# PWA_1_0.net
KiCad netlist of a schematic drawn in EAGLE
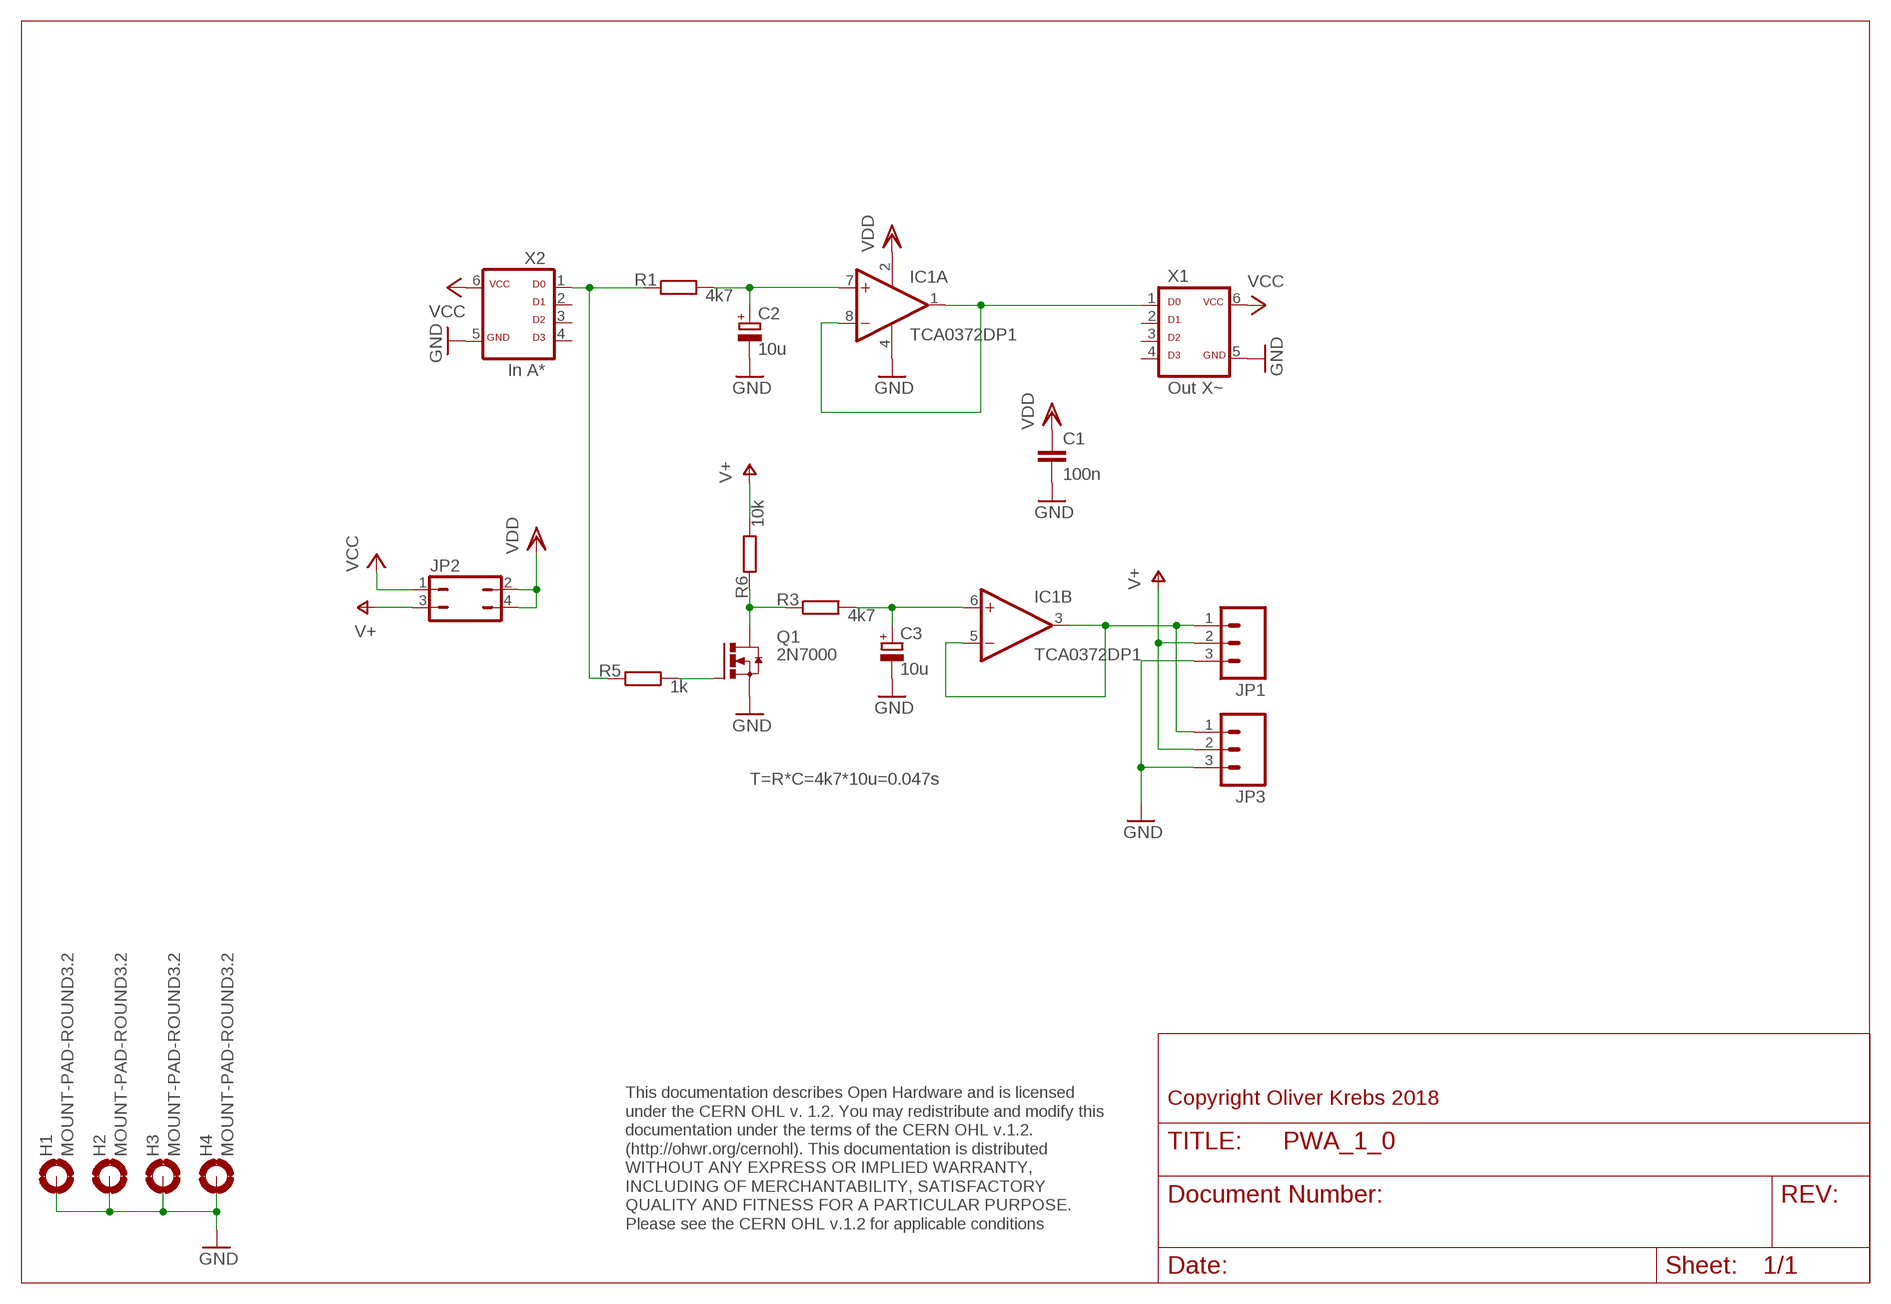
[diagram p0: schematic, sheet 1]

(export (version "E")
  (design (tool "Eeschema 10.0.6"))
  (components
    (comp (ref "C1")
      (value "100n")
      (footprint "eagle-import:C050-025X075")
      (libsource (lib "eagle-import") (part "C-EU050-025X075"))
    )
    (comp (ref "C2")
      (value "10u")
      (footprint "eagle-import:E2-4")
      (libsource (lib "eagle-import") (part "CPOL-EUE2-4"))
    )
    (comp (ref "C3")
      (value "10u")
      (footprint "eagle-import:E2-4")
      (libsource (lib "eagle-import") (part "CPOL-EUE2-4"))
    )
    (comp (ref "H1")
      (value "MOUNT-PAD-ROUND3.2")
      (footprint "eagle-import:3,2-PAD")
      (libsource (lib "eagle-import") (part "MOUNT-PAD-ROUND3.2"))
    )
    (comp (ref "H2")
      (value "MOUNT-PAD-ROUND3.2")
      (footprint "eagle-import:3,2-PAD")
      (libsource (lib "eagle-import") (part "MOUNT-PAD-ROUND3.2"))
    )
    (comp (ref "H3")
      (value "MOUNT-PAD-ROUND3.2")
      (footprint "eagle-import:3,2-PAD")
      (libsource (lib "eagle-import") (part "MOUNT-PAD-ROUND3.2"))
    )
    (comp (ref "H4")
      (value "MOUNT-PAD-ROUND3.2")
      (footprint "eagle-import:3,2-PAD")
      (libsource (lib "eagle-import") (part "MOUNT-PAD-ROUND3.2"))
    )
    (comp (ref "IC1")
      (value "TCA0372DP1")
      (footprint "eagle-import:DIL08")
      (libsource (lib "eagle-import") (part "TCA0372DP1"))
    )
    (comp (ref "JP1")
      (value "M03PTH")
      (footprint "eagle-import:1X03")
      (libsource (lib "eagle-import") (part "M03PTH"))
    )
    (comp (ref "JP2")
      (value "JP2Q")
      (footprint "eagle-import:JP2Q")
      (libsource (lib "eagle-import") (part "JP2Q"))
    )
    (comp (ref "JP3")
      (value "M03BIG_5.08")
      (footprint "eagle-import:1X03_BIG_5.08")
      (libsource (lib "eagle-import") (part "M03BIG_5.08"))
    )
    (comp (ref "Q1")
      (value "2N7000")
      (footprint "eagle-import:TO92-LINE")
      (libsource (lib "eagle-import") (part "2N7000"))
    )
    (comp (ref "R1")
      (value "4k7")
      (footprint "eagle-import:0207_10")
      (libsource (lib "eagle-import") (part "R-EU_0207/10"))
    )
    (comp (ref "R3")
      (value "4k7")
      (footprint "eagle-import:0207_10")
      (libsource (lib "eagle-import") (part "R-EU_0207/10"))
    )
    (comp (ref "R5")
      (value "1k")
      (footprint "eagle-import:0207_10")
      (libsource (lib "eagle-import") (part "R-EU_0207/10"))
    )
    (comp (ref "R6")
      (value "10k")
      (footprint "eagle-import:0207_10")
      (libsource (lib "eagle-import") (part "R-EU_0207/10"))
    )
    (comp (ref "X1")
      (value "Out X~")
      (footprint "eagle-import:ML-6")
      (libsource (lib "eagle-import") (part "ML6D"))
    )
    (comp (ref "X2")
      (value "In A*")
      (footprint "eagle-import:ML-6")
      (libsource (lib "eagle-import") (part "ML6D"))
    )
  )
  (nets
    (net (code "1") (name "GND") (class "Default")
      (node (ref "C1") (pin "2") (pinfunction "2_2") (pintype "passive"))
      (node (ref "C2") (pin "-") (pinfunction "-_-") (pintype "passive"))
      (node (ref "C3") (pin "-") (pinfunction "-_-") (pintype "passive"))
      (node (ref "H1") (pin "B3,2") (pinfunction "MOUNT_B3,2") (pintype "passive"))
      (node (ref "H2") (pin "B3,2") (pinfunction "MOUNT_B3,2") (pintype "passive"))
      (node (ref "H3") (pin "B3,2") (pinfunction "MOUNT_B3,2") (pintype "passive"))
      (node (ref "H4") (pin "B3,2") (pinfunction "MOUNT_B3,2") (pintype "passive"))
      (node (ref "IC1") (pin "4") (pinfunction "GND_4") (pintype "power_in"))
      (node (ref "JP1") (pin "3") (pinfunction "3_3") (pintype "passive"))
      (node (ref "JP3") (pin "3") (pinfunction "3_3") (pintype "passive"))
      (node (ref "Q1") (pin "3") (pinfunction "S_3") (pintype "passive"))
      (node (ref "X1") (pin "5") (pinfunction "5_5") (pintype "passive"))
      (node (ref "X2") (pin "5") (pinfunction "5_5") (pintype "passive"))
    )
    (net (code "2") (name "Net-(IC1A-+IN)") (class "Default")
      (node (ref "C2") (pin "+") (pinfunction "+_+") (pintype "passive"))
      (node (ref "IC1") (pin "7") (pinfunction "+IN_7") (pintype "input"))
      (node (ref "R1") (pin "2") (pinfunction "2_2") (pintype "passive"))
    )
    (net (code "3") (name "Net-(IC1A--IN)") (class "Default")
      (node (ref "IC1") (pin "1") (pinfunction "OUT_1") (pintype "output"))
      (node (ref "IC1") (pin "8") (pinfunction "-IN_8") (pintype "input"))
      (node (ref "X1") (pin "1") (pinfunction "1_1") (pintype "passive"))
    )
    (net (code "4") (name "Net-(IC1B-+IN)") (class "Default")
      (node (ref "C3") (pin "+") (pinfunction "+_+") (pintype "passive"))
      (node (ref "IC1") (pin "6") (pinfunction "+IN_6") (pintype "input"))
      (node (ref "R3") (pin "2") (pinfunction "2_2") (pintype "passive"))
    )
    (net (code "5") (name "Net-(IC1B--IN)") (class "Default")
      (node (ref "IC1") (pin "3") (pinfunction "OUT_3") (pintype "output"))
      (node (ref "IC1") (pin "5") (pinfunction "-IN_5") (pintype "input"))
      (node (ref "JP1") (pin "1") (pinfunction "1_1") (pintype "passive"))
      (node (ref "JP3") (pin "1") (pinfunction "1_1") (pintype "passive"))
    )
    (net (code "6") (name "Net-(Q1-D)") (class "Default")
      (node (ref "Q1") (pin "1") (pinfunction "D_1") (pintype "passive"))
      (node (ref "R3") (pin "1") (pinfunction "1_1") (pintype "passive"))
      (node (ref "R6") (pin "1") (pinfunction "1_1") (pintype "passive"))
    )
    (net (code "7") (name "Net-(Q1-G)") (class "Default")
      (node (ref "Q1") (pin "2") (pinfunction "G_2") (pintype "passive"))
      (node (ref "R5") (pin "2") (pinfunction "2_2") (pintype "passive"))
    )
    (net (code "8") (name "Net-(R1-Pad1)") (class "Default")
      (node (ref "R1") (pin "1") (pinfunction "1_1") (pintype "passive"))
      (node (ref "R5") (pin "1") (pinfunction "1_1") (pintype "passive"))
      (node (ref "X2") (pin "1") (pinfunction "1_1") (pintype "passive"))
    )
    (net (code "9") (name "V+") (class "Default")
      (node (ref "JP1") (pin "2") (pinfunction "2_2") (pintype "passive"))
      (node (ref "JP2") (pin "3") (pinfunction "3_3") (pintype "passive"))
      (node (ref "JP3") (pin "2") (pinfunction "2_2") (pintype "passive"))
      (node (ref "R6") (pin "2") (pinfunction "2_2") (pintype "passive"))
    )
    (net (code "10") (name "VCC") (class "Default")
      (node (ref "JP2") (pin "1") (pinfunction "1_1") (pintype "passive"))
      (node (ref "X1") (pin "6") (pinfunction "6_6") (pintype "passive"))
      (node (ref "X2") (pin "6") (pinfunction "6_6") (pintype "passive"))
    )
    (net (code "11") (name "VDD") (class "Default")
      (node (ref "C1") (pin "1") (pinfunction "1_1") (pintype "passive"))
      (node (ref "IC1") (pin "2") (pinfunction "VDD_2") (pintype "power_in"))
      (node (ref "JP2") (pin "2") (pinfunction "2_2") (pintype "passive"))
      (node (ref "JP2") (pin "4") (pinfunction "4_4") (pintype "passive"))
    )
    (net (code "12") (name "unconnected-(X1-Pad2)") (class "Default")
      (node (ref "X1") (pin "2") (pinfunction "2_2") (pintype "passive"))
    )
    (net (code "13") (name "unconnected-(X1-Pad3)") (class "Default")
      (node (ref "X1") (pin "3") (pinfunction "3_3") (pintype "passive"))
    )
    (net (code "14") (name "unconnected-(X1-Pad4)") (class "Default")
      (node (ref "X1") (pin "4") (pinfunction "4_4") (pintype "passive"))
    )
    (net (code "15") (name "unconnected-(X2-Pad2)") (class "Default")
      (node (ref "X2") (pin "2") (pinfunction "2_2") (pintype "passive"))
    )
    (net (code "16") (name "unconnected-(X2-Pad3)") (class "Default")
      (node (ref "X2") (pin "3") (pinfunction "3_3") (pintype "passive"))
    )
    (net (code "17") (name "unconnected-(X2-Pad4)") (class "Default")
      (node (ref "X2") (pin "4") (pinfunction "4_4") (pintype "passive"))
    )
  )
)
